# Power.net
KiCad netlist of a schematic drawn in Altium Designer
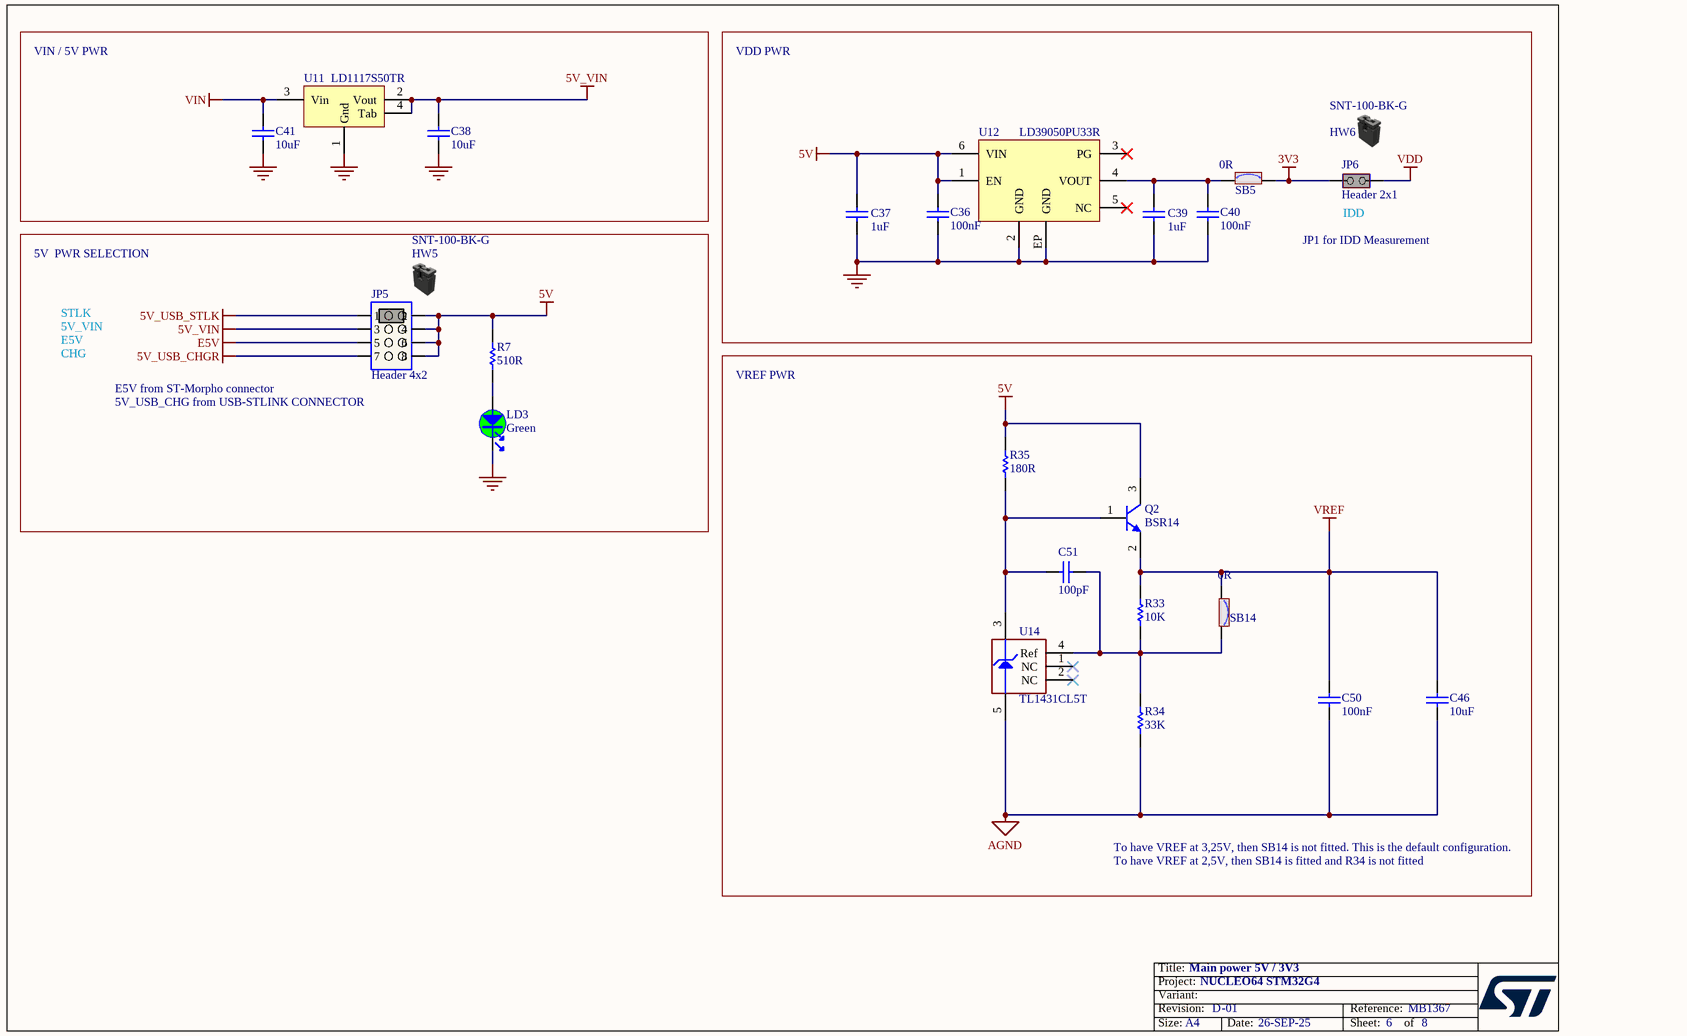
[diagram p0: Power.SchDoc]

(export (version "E")
  (design (tool "Eeschema 10.0.6"))
  (components
    (comp (ref "C36")
      (value "100nF")
      (footprint "C0402")
      (description "Capacitor, MLCC, 100nF, 16V, X7R, +/-10%, 0402, T=0.5mm")
      (fields
        (field (name "INTERNAL_PART_NUMBER") "MCD-00006")
        (field (name "MANUFACTURER_PART_NUMBER") "CC0402KRX7R7BB104")
      )
      (libsource (lib "MCD_PARTS_database") (part "Capacitor"))
    )
    (comp (ref "C37")
      (value "1uF")
      (footprint "C0603")
      (description "Capacitor, MLCC, 1uF, 16V, X5R, 10%, 0603, T=0,8mm")
      (fields
        (field (name "INTERNAL_PART_NUMBER") "MCD-00010")
        (field (name "MANUFACTURER_PART_NUMBER") "CC0603KRX5R7BB105")
        (field (name "PROVIDED_BY") "Subcon")
      )
      (libsource (lib "MCD_PARTS_database") (part "Capacitor"))
    )
    (comp (ref "C38")
      (value "10uF")
      (footprint "C0805")
      (description "Capacitor, MLCC, 10uF, 25V, X5R, 10%, 0805, T=0,85mm")
      (fields
        (field (name "INTERNAL_PART_NUMBER") "MCD-00014")
        (field (name "MANUFACTURER_PART_NUMBER") "CC0805KRX5R8BB106")
        (field (name "PROVIDED_BY") "SUBCO")
      )
      (libsource (lib "MCD_PARTS_database") (part "Capacitor"))
    )
    (comp (ref "C39")
      (value "1uF")
      (footprint "C0603")
      (description "Capacitor, MLCC, 1uF, 16V, X5R, 10%, 0603, T=0,8mm")
      (fields
        (field (name "INTERNAL_PART_NUMBER") "MCD-00010")
        (field (name "MANUFACTURER_PART_NUMBER") "CC0603KRX5R7BB105")
        (field (name "PROVIDED_BY") "Subcon")
      )
      (libsource (lib "MCD_PARTS_database") (part "Capacitor"))
    )
    (comp (ref "C40")
      (value "100nF")
      (footprint "C0402")
      (description "Capacitor, MLCC, 100nF, 16V, X7R, +/-10%, 0402, T=0.5mm")
      (fields
        (field (name "INTERNAL_PART_NUMBER") "MCD-00006")
        (field (name "MANUFACTURER_PART_NUMBER") "CC0402KRX7R7BB104")
      )
      (libsource (lib "MCD_PARTS_database") (part "Capacitor"))
    )
    (comp (ref "C41")
      (value "10uF")
      (footprint "C0805")
      (description "Capacitor, MLCC, 10uF, 25V, X5R, 10%, 0805, T=0,85mm")
      (fields
        (field (name "INTERNAL_PART_NUMBER") "MCD-00014")
        (field (name "MANUFACTURER_PART_NUMBER") "CC0805KRX5R8BB106")
        (field (name "PROVIDED_BY") "SUBCO")
      )
      (libsource (lib "MCD_PARTS_database") (part "Capacitor"))
    )
    (comp (ref "C46")
      (value "10uF")
      (footprint "C0603")
      (description "Capacitor, MLCC, 10uF, 10V, X5R, 10%, 0603, T=0.8mm")
      (fields
        (field (name "INTERNAL_PART_NUMBER") "MCD-01124")
        (field (name "MANUFACTURER_PART_NUMBER") "GRM188R61A106KAAL")
        (field (name "PROVIDED_BY") "SUBCO")
      )
      (libsource (lib "MCD_PARTS_database") (part "Capacitor"))
    )
    (comp (ref "C50")
      (value "100nF")
      (footprint "C0603")
      (description "Capacitor, MLCC, 100nF, 16V, X7R, 10%, 0603, T=0,8mm")
      (fields
        (field (name "INTERNAL_PART_NUMBER") "MCD-00211")
        (field (name "MANUFACTURER_PART_NUMBER") "CC0603KRX7R7BB104")
        (field (name "PROVIDED_BY") "SUBCO")
      )
      (libsource (lib "MCD_PARTS_database") (part "Capacitor"))
    )
    (comp (ref "C51")
      (value "100pF")
      (footprint "C0603")
      (description "Capacitor,100pF,50V,X7R,10%,0603")
      (fields
        (field (name "INTERNAL_PART_NUMBER") "MCD-01101")
        (field (name "MANUFACTURER_PART_NUMBER") "06035C101JAT4A")
        (field (name "PROVIDED_BY") "SUBCO")
      )
      (libsource (lib "MCD_PARTS_database") (part "Capacitor"))
    )
    (comp (ref "HW5")
      (value "SNT-100-BK-G")
      (description "SHUNT 2.54mm BLACK")
      (fields
        (field (name "INTERNAL_PART_NUMBER") "MCD-00043")
        (field (name "MANUFACTURER") "SAMTEC")
        (field (name "PROVIDED_BY") "Subcon")
      )
      (libsource (lib "MCD_PARTS_database") (part "Shunt Black 2.54mm"))
    )
    (comp (ref "HW6")
      (value "SNT-100-BK-G")
      (description "SHUNT 2.54mm BLACK")
      (fields
        (field (name "INTERNAL_PART_NUMBER") "MCD-00043")
        (field (name "MANUFACTURER") "SAMTEC")
        (field (name "PROVIDED_BY") "Subcon")
      )
      (libsource (lib "MCD_PARTS_database") (part "Shunt Black 2.54mm"))
    )
    (comp (ref "JP5")
      (value "Header 4x2")
      (footprint "CON_SAMTEC_TSW-104-07-X-D")
      (description "Header, 4x2, 2,54mm, VR, TH, Height 5.84mm/2.54mm - Shunt Fitted 1-2")
      (fields
        (field (name "INTERNAL_PART_NUMBER") "MCD-00686")
        (field (name "MANUFACTURER_PART_NUMBER") "TSW-104-07-G-D")
        (field (name "PROVIDED_BY") "SUBCO")
      )
      (libsource (lib "MCD_PARTS_database") (part "Jumper_Header 4x2 Fitted 1-2"))
    )
    (comp (ref "JP6")
      (value "Header 2x1")
      (footprint "CON_SAMTEC_TSW-102-07-G-S")
      (description "Header, 2x1, 2,54mm, VR, TH, Height 5.84mm/2.54mm - Shunt Fitted by default")
      (fields
        (field (name "INTERNAL_PART_NUMBER") "MCD-00683")
        (field (name "MANUFACTURER_PART_NUMBER") "TSW-102-07-G-S")
        (field (name "PROVIDED_BY") "Subcon")
      )
      (libsource (lib "MCD_PARTS_database") (part "Jumper_Header 2x1 Fitted"))
    )
    (comp (ref "LD3")
      (value "Green")
      (footprint "LED_0603_GREEN")
      (description "LED, Green, 2V, 20mA, 0603")
      (fields (field (name "INTERNAL_PART_NUMBER") "MCD-02900") (field (name "MANUFACTURER") "EVERLIGHT"))
      (libsource (lib "MCD_PARTS_database") (part "LED_green"))
    )
    (comp (ref "Q2")
      (value "BSR14")
      (footprint "NPN_SOT23")
      (description "NPN Bipolar Transistor")
      (fields
        (field (name "INTERNAL_PART_NUMBER") "MCD-00073")
        (field (name "MANUFACTURER") "ON SEMICONDUCTOR")
        (field (name "PROVIDED_BY") "SUBCO")
      )
      (libsource (lib "MCD_PARTS_database") (part "9013-SOT23"))
    )
    (comp (ref "R7")
      (value "510R")
      (footprint "R0603")
      (description "Resistor,510R,0603,1%,1/10W")
      (fields
        (field (name "INTERNAL_PART_NUMBER") "MCD-00225")
        (field (name "MANUFACTURER_PART_NUMBER") "RC0603FR-07510RL")
        (field (name "PROVIDED_BY") "SUBCO")
      )
      (libsource (lib "MCD_PARTS_database") (part "Resistor"))
    )
    (comp (ref "R33")
      (value "10K")
      (footprint "R0603")
      (description "resistor, 10K, 0603, 0.5%, 1/10W")
      (fields
        (field (name "INTERNAL_PART_NUMBER") "MCD-01215")
        (field (name "MANUFACTURER_PART_NUMBER") "RC0603DR-0710KL")
        (field (name "PROVIDED_BY") "SUBCO")
      )
      (libsource (lib "MCD_PARTS_database") (part "Resistor"))
    )
    (comp (ref "R34")
      (value "33K")
      (footprint "R0603")
      (description "Resistor,33K,0603,0.5%,1/10W")
      (fields
        (field (name "INTERNAL_PART_NUMBER") "MCD-01209")
        (field (name "MANUFACTURER_PART_NUMBER") "RC0603DR-0733KL")
        (field (name "PROVIDED_BY") "SUBCO")
      )
      (libsource (lib "MCD_PARTS_database") (part "Resistor"))
    )
    (comp (ref "R35")
      (value "180R")
      (footprint "R0603")
      (description "Resistor,180R,0603,1%,1/10W")
      (fields
        (field (name "INTERNAL_PART_NUMBER") "MCD-00342")
        (field (name "MANUFACTURER_PART_NUMBER") "RC0603FR-07180RL")
        (field (name "PROVIDED_BY") "SUBCO")
      )
      (libsource (lib "MCD_PARTS_database") (part "Resistor"))
    )
    (comp (ref "SB5")
      (value "0R")
      (footprint "SOLDER-BRIDGE_R0603-0R")
      (description "Solder Bridge ON")
      (fields
        (field (name "INTERNAL_PART_NUMBER") "MCD-00071")
        (field (name "MANUFACTURER_PART_NUMBER") "RC0603JR-070RL")
        (field (name "PROVIDED_BY") "SUBCO")
      )
      (libsource (lib "MCD_PARTS_database") (part "SB_ON"))
    )
    (comp (ref "SB14")
      (value "0R")
      (footprint "SOLDER-BRIDGE_R0603-0R")
      (description "Solder Bridge ON")
      (fields
        (field (name "INTERNAL_PART_NUMBER") "MCD-00071")
        (field (name "MANUFACTURER_PART_NUMBER") "RC0603JR-070RL")
        (field (name "PROVIDED_BY") "SUBCO")
      )
      (libsource (lib "") (part "SB_ON_1"))
    )
    (comp (ref "U11")
      (value "LD1117S50TR")
      (footprint "REG_SOT223-TAB")
      (description "IC REG LDO 5V 0.8A SOT223")
      (fields
        (field (name "INTERNAL_PART_NUMBER") "MCD-00088")
        (field (name "MANUFACTURER") "STMICROELECTRONICS")
        (field (name "PROVIDED_BY") "SUBCO with ST control")
      )
      (libsource (lib "MCD_PARTS_database") (part "LD1117S50TR"))
    )
    (comp (ref "U12")
      (value "LD39050PU33R")
      (footprint "ICC_DFN6-EPAD_3X3_P095")
      (description "Low quiescent current and low noise voltage regulators")
      (fields
        (field (name "INTERNAL_PART_NUMBER") "MCD-00215")
        (field (name "MANUFACTURER") "STMICROELECTRONICS")
        (field (name "PROVIDED_BY") "SUBCO with ST control")
      )
      (libsource (lib "MCD_PARTS_database") (part "LD39050PU33R"))
    )
    (comp (ref "U14")
      (value "TL1431CL5T")
      (footprint "ICC_SOT23-5L_H1P45")
      (description "Programmable voltage reference with 0.4% voltage precision")
      (fields
        (field (name "INTERNAL_PART_NUMBER") "MCD-01802")
        (field (name "MANUFACTURER") "STMICROELECTRONICS")
        (field (name "PROVIDED_BY") "SUBCO with ST control")
      )
      (libsource (lib "MCD_PARTS_database") (part "TL1431ACL5T"))
    )
  )
  (nets
    (net (code "1") (name "3V3") (class "Default")
      (node (ref "JP6") (pin "1") (pinfunction "COMMON_1") (pintype "passive"))
      (node (ref "SB5") (pin "2") (pinfunction "2_2") (pintype "passive"))
    )
    (net (code "2") (name "5V") (class "Default")
      (node (ref "C36") (pin "2") (pinfunction "2_2") (pintype "passive"))
      (node (ref "C37") (pin "2") (pinfunction "2_2") (pintype "passive"))
      (node (ref "JP5") (pin "2") (pinfunction "2_2") (pintype "passive"))
      (node (ref "JP5") (pin "4") (pinfunction "4_4") (pintype "passive"))
      (node (ref "JP5") (pin "6") (pinfunction "6_6") (pintype "passive"))
      (node (ref "JP5") (pin "8") (pinfunction "8_8") (pintype "passive"))
      (node (ref "Q2") (pin "3") (pinfunction "C_3") (pintype "passive"))
      (node (ref "R35") (pin "2") (pinfunction "2_2") (pintype "passive"))
      (node (ref "R7") (pin "2") (pinfunction "2_2") (pintype "passive"))
      (node (ref "U12") (pin "1") (pinfunction "EN_1") (pintype "passive"))
      (node (ref "U12") (pin "6") (pinfunction "VIN_6") (pintype "passive"))
    )
    (net (code "3") (name "5V_USB_CHGR") (class "Default")
      (node (ref "JP5") (pin "7") (pinfunction "7_7") (pintype "passive"))
    )
    (net (code "4") (name "5V_USB_STLK") (class "Default")
      (node (ref "JP5") (pin "1") (pinfunction "1_1") (pintype "passive"))
    )
    (net (code "5") (name "5V_VIN") (class "Default")
      (node (ref "C38") (pin "2") (pinfunction "2_2") (pintype "passive"))
      (node (ref "JP5") (pin "3") (pinfunction "3_3") (pintype "passive"))
      (node (ref "U11") (pin "2") (pinfunction "Vout_2") (pintype "passive"))
      (node (ref "U11") (pin "4") (pinfunction "Tab_4") (pintype "passive"))
    )
    (net (code "6") (name "AGND") (class "Default")
      (node (ref "C46") (pin "1") (pinfunction "1_1") (pintype "passive"))
      (node (ref "C50") (pin "1") (pinfunction "1_1") (pintype "passive"))
      (node (ref "R34") (pin "1") (pinfunction "1_1") (pintype "passive"))
      (node (ref "U14") (pin "5") (pinfunction "Anode_5") (pintype "passive"))
    )
    (net (code "7") (name "E5V") (class "Default")
      (node (ref "JP5") (pin "5") (pinfunction "5_5") (pintype "passive"))
    )
    (net (code "8") (name "GND") (class "Default")
      (node (ref "C36") (pin "1") (pinfunction "1_1") (pintype "passive"))
      (node (ref "C37") (pin "1") (pinfunction "1_1") (pintype "passive"))
      (node (ref "C38") (pin "1") (pinfunction "1_1") (pintype "passive"))
      (node (ref "C39") (pin "1") (pinfunction "1_1") (pintype "passive"))
      (node (ref "C40") (pin "1") (pinfunction "1_1") (pintype "passive"))
      (node (ref "C41") (pin "1") (pinfunction "1_1") (pintype "passive"))
      (node (ref "LD3") (pin "2") (pintype "passive"))
      (node (ref "U11") (pin "1") (pinfunction "Gnd_1") (pintype "passive"))
      (node (ref "U12") (pin "2") (pinfunction "GND_2") (pintype "passive"))
      (node (ref "U12") (pin "EP") (pinfunction "GND_EP") (pintype "passive"))
    )
    (net (code "9") (name "Net-(LD3-Pad1)") (class "Default")
      (node (ref "LD3") (pin "1") (pintype "passive"))
      (node (ref "R7") (pin "1") (pinfunction "1_1") (pintype "passive"))
    )
    (net (code "10") (name "Net-(Q2-B)") (class "Default")
      (node (ref "C51") (pin "1") (pinfunction "1_1") (pintype "passive"))
      (node (ref "Q2") (pin "1") (pinfunction "B_1") (pintype "passive"))
      (node (ref "R35") (pin "1") (pinfunction "1_1") (pintype "passive"))
      (node (ref "U14") (pin "3") (pinfunction "Cathode_3") (pintype "passive"))
    )
    (net (code "11") (name "Net-(U12-VOUT)") (class "Default")
      (node (ref "C39") (pin "2") (pinfunction "2_2") (pintype "passive"))
      (node (ref "C40") (pin "2") (pinfunction "2_2") (pintype "passive"))
      (node (ref "SB5") (pin "1") (pinfunction "1_1") (pintype "passive"))
      (node (ref "U12") (pin "4") (pinfunction "VOUT_4") (pintype "passive"))
    )
    (net (code "12") (name "Net-(U14-Ref)") (class "Default")
      (node (ref "C51") (pin "2") (pinfunction "2_2") (pintype "passive"))
      (node (ref "R33") (pin "1") (pinfunction "1_1") (pintype "passive"))
      (node (ref "R34") (pin "2") (pinfunction "2_2") (pintype "passive"))
      (node (ref "SB14") (pin "2") (pinfunction "2_2") (pintype "passive"))
      (node (ref "U14") (pin "4") (pinfunction "Ref_4") (pintype "passive"))
    )
    (net (code "13") (name "VDD") (class "Default")
      (node (ref "JP6") (pin "2") (pinfunction "NO_2") (pintype "passive"))
    )
    (net (code "14") (name "VIN") (class "Default")
      (node (ref "C41") (pin "2") (pinfunction "2_2") (pintype "passive"))
      (node (ref "U11") (pin "3") (pinfunction "Vin_3") (pintype "passive"))
    )
    (net (code "15") (name "VREF") (class "Default")
      (node (ref "C46") (pin "2") (pinfunction "2_2") (pintype "passive"))
      (node (ref "C50") (pin "2") (pinfunction "2_2") (pintype "passive"))
      (node (ref "Q2") (pin "2") (pinfunction "E_2") (pintype "passive"))
      (node (ref "R33") (pin "2") (pinfunction "2_2") (pintype "passive"))
      (node (ref "SB14") (pin "1") (pinfunction "1_1") (pintype "passive"))
    )
    (net (code "16") (name "unconnected-(U12-NC-Pad5)") (class "Default")
      (node (ref "U12") (pin "5") (pinfunction "NC_5") (pintype "passive+no_connect"))
    )
    (net (code "17") (name "unconnected-(U12-PG-Pad3)") (class "Default")
      (node (ref "U12") (pin "3") (pinfunction "PG_3") (pintype "passive+no_connect"))
    )
    (net (code "18") (name "unconnected-(U14-NC-Pad1)") (class "Default")
      (node (ref "U14") (pin "1") (pinfunction "NC_1") (pintype "passive+no_connect"))
    )
    (net (code "19") (name "unconnected-(U14-NC-Pad2)") (class "Default")
      (node (ref "U14") (pin "2") (pinfunction "NC_2") (pintype "passive+no_connect"))
    )
  )
)
